# tick-shield-mk-1_3.net
KiCad netlist of a schematic drawn in EAGLE
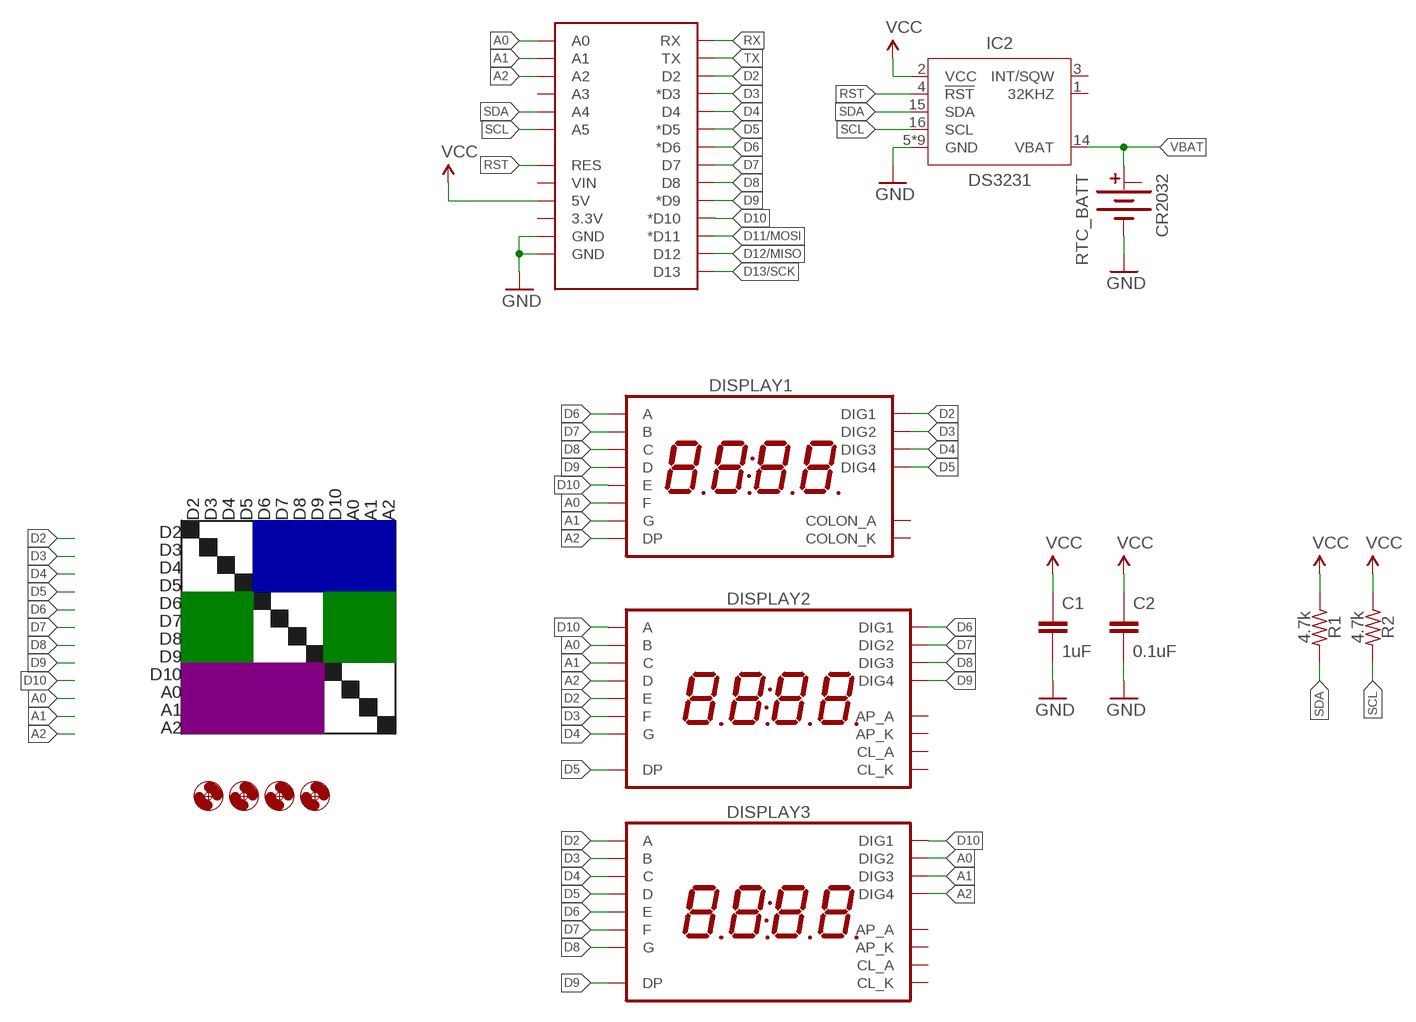
[diagram p0: schematic, sheet 1]

(export (version "E")
  (design (tool "Eeschema 10.0.6"))
  (components
    (comp (ref "C1")
      (value "1uF")
      (footprint "eagle-import:C025-024X044")
      (libsource (lib "eagle-import") (part "CAPACITOR-CERAMIC025-024X044"))
    )
    (comp (ref "C2")
      (value "0.1uF")
      (footprint "eagle-import:C025-024X044")
      (libsource (lib "eagle-import") (part "CAPACITOR-CERAMIC025-024X044"))
    )
    (comp (ref "DISPLAY1")
      (value "7SEG_4DIGIT_COLON14.2MM-CC-NS")
      (footprint "eagle-import:7SEG_4DIG_NS")
      (libsource (lib "eagle-import") (part "7SEG_4DIGIT_COLON14.2MM-CC-NS"))
    )
    (comp (ref "DISPLAY2")
      (value "7SEG_4DIGIT_COLON_APOS")
      (footprint "eagle-import:7SEG_4DIG_10MM")
      (libsource (lib "eagle-import") (part "7SEG_4DIGIT_COLON_APOS"))
    )
    (comp (ref "DISPLAY3")
      (value "7SEG_4DIGIT_COLON_APOS")
      (footprint "eagle-import:7SEG_4DIG_10MM")
      (libsource (lib "eagle-import") (part "7SEG_4DIGIT_COLON_APOS"))
    )
    (comp (ref "H1")
      (value "HOLE#2")
      (footprint "eagle-import:HOLE-#2")
      (libsource (lib "eagle-import") (part "HOLE#2"))
    )
    (comp (ref "H2")
      (value "HOLE#2")
      (footprint "eagle-import:HOLE-#2")
      (libsource (lib "eagle-import") (part "HOLE#2"))
    )
    (comp (ref "H3")
      (value "HOLE#2")
      (footprint "eagle-import:HOLE-#2")
      (libsource (lib "eagle-import") (part "HOLE#2"))
    )
    (comp (ref "H4")
      (value "HOLE#2")
      (footprint "eagle-import:HOLE-#2")
      (libsource (lib "eagle-import") (part "HOLE#2"))
    )
    (comp (ref "IC2")
      (value "DS3231")
      (footprint "eagle-import:SO16W")
      (libsource (lib "eagle-import") (part "DS3231"))
    )
    (comp (ref "R1")
      (value "4.7k")
      (footprint "eagle-import:RESISTOR-AXIAL-PTH-6.35MM")
      (libsource (lib "eagle-import") (part "RESISTORPTH-AXIAL-6.35MM"))
    )
    (comp (ref "R2")
      (value "4.7k")
      (footprint "eagle-import:RESISTOR-AXIAL-PTH-6.35MM")
      (libsource (lib "eagle-import") (part "RESISTORPTH-AXIAL-6.35MM"))
    )
    (comp (ref "RTC_BATT")
      (value "CR2032")
      (footprint "eagle-import:BATTCON_20MM_MINE")
      (libsource (lib "eagle-import") (part "BATTERY-COINCR2032_SMD"))
    )
    (comp (ref "U$1")
      (value "ARDUINO_SHIELD_SMALLER")
      (footprint "eagle-import:ARDUINO_SHIELD_NOOUTLINE_INSIDE_SMALLER")
      (libsource (lib "eagle-import") (part "ARDUINO_SHIELD_SMALLER"))
    )
  )
  (nets
    (net (code "1") (name "A0") (class "Default")
      (node (ref "DISPLAY1") (pin "P$12") (pinfunction "F_P$12") (pintype "passive"))
      (node (ref "DISPLAY2") (pin "16") (pinfunction "B_16") (pintype "passive"))
      (node (ref "DISPLAY3") (pin "2") (pinfunction "DIG2_2") (pintype "passive"))
      (node (ref "U$1") (pin "A0") (pinfunction "A0_A0") (pintype "bidirectional"))
    )
    (net (code "2") (name "A1") (class "Default")
      (node (ref "DISPLAY1") (pin "P$5") (pinfunction "G_P$5") (pintype "passive"))
      (node (ref "DISPLAY2") (pin "13") (pinfunction "C_13") (pintype "passive"))
      (node (ref "DISPLAY3") (pin "6") (pinfunction "DIG3_6") (pintype "passive"))
      (node (ref "U$1") (pin "A1") (pinfunction "A1_A1") (pintype "bidirectional"))
    )
    (net (code "3") (name "A2") (class "Default")
      (node (ref "DISPLAY1") (pin "P$3") (pinfunction "DP_P$3") (pintype "passive"))
      (node (ref "DISPLAY2") (pin "3") (pinfunction "D_3") (pintype "passive"))
      (node (ref "DISPLAY3") (pin "8") (pinfunction "DIG4_8") (pintype "passive"))
      (node (ref "U$1") (pin "A2") (pinfunction "A2_A2") (pintype "bidirectional"))
    )
    (net (code "4") (name "D2") (class "Default")
      (node (ref "DISPLAY1") (pin "P$14") (pinfunction "DIG1_P$14") (pintype "passive"))
      (node (ref "DISPLAY2") (pin "5") (pinfunction "E_5") (pintype "passive"))
      (node (ref "DISPLAY3") (pin "14") (pinfunction "A_14") (pintype "passive"))
      (node (ref "U$1") (pin "D2") (pinfunction "D2_D2") (pintype "bidirectional"))
    )
    (net (code "5") (name "D3") (class "Default")
      (node (ref "DISPLAY1") (pin "P$11") (pinfunction "DIG2_P$11") (pintype "passive"))
      (node (ref "DISPLAY2") (pin "11") (pinfunction "F_11") (pintype "passive"))
      (node (ref "DISPLAY3") (pin "16") (pinfunction "B_16") (pintype "passive"))
      (node (ref "U$1") (pin "D3") (pinfunction "*D3_D3") (pintype "bidirectional"))
    )
    (net (code "6") (name "D4") (class "Default")
      (node (ref "DISPLAY1") (pin "P$10") (pinfunction "DIG3_P$10") (pintype "passive"))
      (node (ref "DISPLAY2") (pin "15") (pinfunction "G_15") (pintype "passive"))
      (node (ref "DISPLAY3") (pin "13") (pinfunction "C_13") (pintype "passive"))
      (node (ref "U$1") (pin "D4") (pinfunction "D4_D4") (pintype "bidirectional"))
    )
    (net (code "7") (name "D5") (class "Default")
      (node (ref "DISPLAY1") (pin "P$6") (pinfunction "DIG4_P$6") (pintype "passive"))
      (node (ref "DISPLAY2") (pin "7") (pinfunction "DP_7") (pintype "passive"))
      (node (ref "DISPLAY3") (pin "3") (pinfunction "D_3") (pintype "passive"))
      (node (ref "U$1") (pin "D5") (pinfunction "*D5_D5") (pintype "bidirectional"))
    )
    (net (code "8") (name "D6") (class "Default")
      (node (ref "DISPLAY1") (pin "P$13") (pinfunction "A_P$13") (pintype "passive"))
      (node (ref "DISPLAY2") (pin "1") (pinfunction "DIG1_1") (pintype "passive"))
      (node (ref "DISPLAY3") (pin "5") (pinfunction "E_5") (pintype "passive"))
      (node (ref "U$1") (pin "D6") (pinfunction "*D6_D6") (pintype "bidirectional"))
    )
    (net (code "9") (name "D7") (class "Default")
      (node (ref "DISPLAY1") (pin "P$9") (pinfunction "B_P$9") (pintype "passive"))
      (node (ref "DISPLAY2") (pin "2") (pinfunction "DIG2_2") (pintype "passive"))
      (node (ref "DISPLAY3") (pin "11") (pinfunction "F_11") (pintype "passive"))
      (node (ref "U$1") (pin "D7") (pinfunction "D7_D7") (pintype "bidirectional"))
    )
    (net (code "10") (name "D8") (class "Default")
      (node (ref "DISPLAY1") (pin "P$4") (pinfunction "C_P$4") (pintype "passive"))
      (node (ref "DISPLAY2") (pin "6") (pinfunction "DIG3_6") (pintype "passive"))
      (node (ref "DISPLAY3") (pin "15") (pinfunction "G_15") (pintype "passive"))
      (node (ref "U$1") (pin "D8") (pinfunction "D8_D8") (pintype "bidirectional"))
    )
    (net (code "11") (name "D9") (class "Default")
      (node (ref "DISPLAY1") (pin "P$2") (pinfunction "D_P$2") (pintype "passive"))
      (node (ref "DISPLAY2") (pin "8") (pinfunction "DIG4_8") (pintype "passive"))
      (node (ref "DISPLAY3") (pin "7") (pinfunction "DP_7") (pintype "passive"))
      (node (ref "U$1") (pin "D9") (pinfunction "*D9_D9") (pintype "bidirectional"))
    )
    (net (code "12") (name "D10") (class "Default")
      (node (ref "DISPLAY1") (pin "P$1") (pinfunction "E_P$1") (pintype "passive"))
      (node (ref "DISPLAY2") (pin "14") (pinfunction "A_14") (pintype "passive"))
      (node (ref "DISPLAY3") (pin "1") (pinfunction "DIG1_1") (pintype "passive"))
      (node (ref "U$1") (pin "D10") (pinfunction "*D10_D10") (pintype "bidirectional"))
    )
    (net (code "13") (name "D11{slash}MOSI") (class "Default")
      (node (ref "U$1") (pin "D11") (pinfunction "*D11_D11") (pintype "bidirectional"))
    )
    (net (code "14") (name "D12{slash}MISO") (class "Default")
      (node (ref "U$1") (pin "D12") (pinfunction "D12_D12") (pintype "bidirectional"))
    )
    (net (code "15") (name "D13{slash}SCK") (class "Default")
      (node (ref "U$1") (pin "D13") (pinfunction "D13_D13") (pintype "bidirectional"))
    )
    (net (code "16") (name "GND") (class "Default")
      (node (ref "C1") (pin "2") (pinfunction "2_2") (pintype "passive"))
      (node (ref "C2") (pin "2") (pinfunction "2_2") (pintype "passive"))
      (node (ref "IC2") (pin "10") (pinfunction "GND_10") (pintype "bidirectional"))
      (node (ref "IC2") (pin "11") (pinfunction "GND_11") (pintype "bidirectional"))
      (node (ref "IC2") (pin "12") (pinfunction "GND_12") (pintype "bidirectional"))
      (node (ref "IC2") (pin "13") (pinfunction "GND_13") (pintype "bidirectional"))
      (node (ref "IC2") (pin "5") (pinfunction "GND_5") (pintype "bidirectional"))
      (node (ref "IC2") (pin "6") (pinfunction "GND_6") (pintype "bidirectional"))
      (node (ref "IC2") (pin "7") (pinfunction "GND_7") (pintype "bidirectional"))
      (node (ref "IC2") (pin "8") (pinfunction "GND_8") (pintype "bidirectional"))
      (node (ref "IC2") (pin "9") (pinfunction "GND_9") (pintype "bidirectional"))
      (node (ref "RTC_BATT") (pin "BOTTOM") (pinfunction "-_BOTTOM") (pintype "bidirectional"))
      (node (ref "U$1") (pin "GND@0") (pinfunction "GND_GND@0") (pintype "bidirectional"))
      (node (ref "U$1") (pin "GND@1") (pinfunction "GND_GND@1") (pintype "bidirectional"))
    )
    (net (code "17") (name "RST") (class "Default")
      (node (ref "IC2") (pin "4") (pinfunction "~{RST}_4") (pintype "bidirectional"))
      (node (ref "U$1") (pin "RES") (pinfunction "RES_RES") (pintype "bidirectional"))
    )
    (net (code "18") (name "RX") (class "Default")
      (node (ref "U$1") (pin "RX") (pinfunction "RX_RX") (pintype "bidirectional"))
    )
    (net (code "19") (name "SCL") (class "Default")
      (node (ref "IC2") (pin "16") (pinfunction "SCL_16") (pintype "bidirectional"))
      (node (ref "R2") (pin "P$2") (pinfunction "2_P$2") (pintype "passive"))
      (node (ref "U$1") (pin "A5") (pinfunction "A5_A5") (pintype "bidirectional"))
    )
    (net (code "20") (name "SDA") (class "Default")
      (node (ref "IC2") (pin "15") (pinfunction "SDA_15") (pintype "bidirectional"))
      (node (ref "R1") (pin "P$2") (pinfunction "2_P$2") (pintype "passive"))
      (node (ref "U$1") (pin "A4") (pinfunction "A4_A4") (pintype "bidirectional"))
    )
    (net (code "21") (name "TX") (class "Default")
      (node (ref "U$1") (pin "TX") (pinfunction "TX_TX") (pintype "bidirectional"))
    )
    (net (code "22") (name "VBAT") (class "Default")
      (node (ref "IC2") (pin "14") (pinfunction "VBAT_14") (pintype "bidirectional"))
      (node (ref "RTC_BATT") (pin "TOP@1") (pinfunction "+_TOP@1") (pintype "bidirectional"))
    )
    (net (code "23") (name "VCC") (class "Default")
      (node (ref "C1") (pin "1") (pinfunction "1_1") (pintype "passive"))
      (node (ref "C2") (pin "1") (pinfunction "1_1") (pintype "passive"))
      (node (ref "IC2") (pin "2") (pinfunction "VCC_2") (pintype "bidirectional"))
      (node (ref "R1") (pin "P$1") (pinfunction "1_P$1") (pintype "passive"))
      (node (ref "R2") (pin "P$1") (pinfunction "1_P$1") (pintype "passive"))
      (node (ref "U$1") (pin "5V") (pinfunction "5V_5V") (pintype "bidirectional"))
    )
    (net (code "24") (name "unconnected-(DISPLAY1-COLON_A-PadP$8)") (class "Default")
      (node (ref "DISPLAY1") (pin "P$8") (pinfunction "COLON_A_P$8") (pintype "passive"))
    )
    (net (code "25") (name "unconnected-(DISPLAY1-COLON_K-PadP$7)") (class "Default")
      (node (ref "DISPLAY1") (pin "P$7") (pinfunction "COLON_K_P$7") (pintype "passive"))
    )
    (net (code "26") (name "unconnected-(DISPLAY2-AP_A-Pad10)") (class "Default")
      (node (ref "DISPLAY2") (pin "10") (pinfunction "AP_A_10") (pintype "bidirectional"))
    )
    (net (code "27") (name "unconnected-(DISPLAY2-AP_K-Pad9)") (class "Default")
      (node (ref "DISPLAY2") (pin "9") (pinfunction "AP_K_9") (pintype "bidirectional"))
    )
    (net (code "28") (name "unconnected-(DISPLAY2-CL_A-Pad4)") (class "Default")
      (node (ref "DISPLAY2") (pin "4") (pinfunction "CL_A_4") (pintype "passive"))
    )
    (net (code "29") (name "unconnected-(DISPLAY2-CL_K-Pad12)") (class "Default")
      (node (ref "DISPLAY2") (pin "12") (pinfunction "CL_K_12") (pintype "passive"))
    )
    (net (code "30") (name "unconnected-(DISPLAY3-AP_A-Pad10)") (class "Default")
      (node (ref "DISPLAY3") (pin "10") (pinfunction "AP_A_10") (pintype "bidirectional"))
    )
    (net (code "31") (name "unconnected-(DISPLAY3-AP_K-Pad9)") (class "Default")
      (node (ref "DISPLAY3") (pin "9") (pinfunction "AP_K_9") (pintype "bidirectional"))
    )
    (net (code "32") (name "unconnected-(DISPLAY3-CL_A-Pad4)") (class "Default")
      (node (ref "DISPLAY3") (pin "4") (pinfunction "CL_A_4") (pintype "passive"))
    )
    (net (code "33") (name "unconnected-(DISPLAY3-CL_K-Pad12)") (class "Default")
      (node (ref "DISPLAY3") (pin "12") (pinfunction "CL_K_12") (pintype "passive"))
    )
    (net (code "34") (name "unconnected-(IC2-32KHZ-Pad1)") (class "Default")
      (node (ref "IC2") (pin "1") (pinfunction "32KHZ_1") (pintype "bidirectional"))
    )
    (net (code "35") (name "unconnected-(IC2-INT{slash}SQW-Pad3)") (class "Default")
      (node (ref "IC2") (pin "3") (pinfunction "INT/SQW_3") (pintype "bidirectional"))
    )
    (net (code "36") (name "unconnected-(RTC_BATT-+1-PadTOP@2)") (class "Default")
      (node (ref "RTC_BATT") (pin "TOP@2") (pinfunction "+1_TOP@2") (pintype "bidirectional"))
    )
    (net (code "37") (name "unconnected-(U$1-Pad3.3V)") (class "Default")
      (node (ref "U$1") (pin "3.3V") (pinfunction "3.3V_3.3V") (pintype "bidirectional"))
    )
    (net (code "38") (name "unconnected-(U$1-PadA3)") (class "Default")
      (node (ref "U$1") (pin "A3") (pinfunction "A3_A3") (pintype "bidirectional"))
    )
    (net (code "39") (name "unconnected-(U$1-PadVIN)") (class "Default")
      (node (ref "U$1") (pin "VIN") (pinfunction "VIN_VIN") (pintype "bidirectional"))
    )
  )
)
